# AutoThresholdPulseSensor.net
KiCad netlist of a schematic drawn in EAGLE
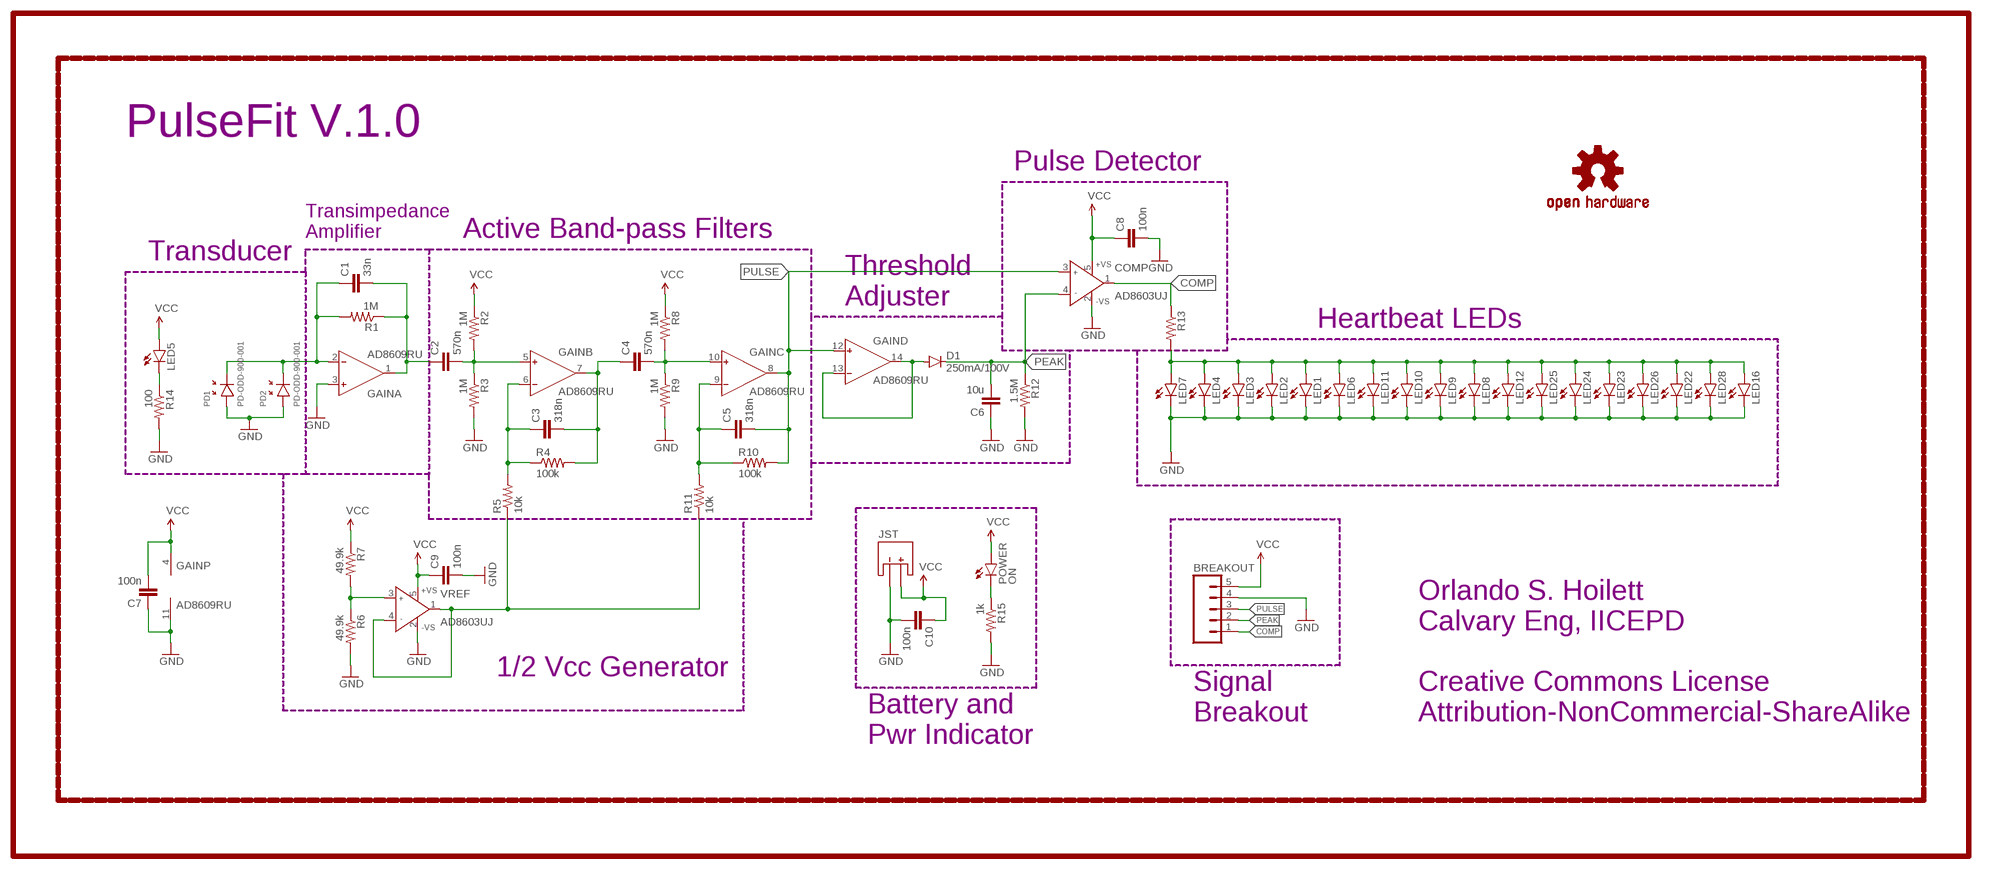
[diagram p0: schematic, sheet 1]

(export (version "E")
  (design (tool "Eeschema 10.0.6"))
  (components
    (comp (ref "BREAKOUT")
      (value "M05NO_SILK")
      (footprint "eagle-import:1X05_NO_SILK")
      (libsource (lib "eagle-import") (part "M05NO_SILK"))
    )
    (comp (ref "C1")
      (value "33n")
      (footprint "eagle-import:C0402")
      (libsource (lib "eagle-import") (part "C-EUC0402"))
    )
    (comp (ref "C2")
      (value "570n")
      (footprint "eagle-import:C0402")
      (libsource (lib "eagle-import") (part "C-EUC0402"))
    )
    (comp (ref "C3")
      (value "318n")
      (footprint "eagle-import:C0402")
      (libsource (lib "eagle-import") (part "C-EUC0402"))
    )
    (comp (ref "C4")
      (value "570n")
      (footprint "eagle-import:C0402")
      (libsource (lib "eagle-import") (part "C-EUC0402"))
    )
    (comp (ref "C5")
      (value "318n")
      (footprint "eagle-import:C0402")
      (libsource (lib "eagle-import") (part "C-EUC0402"))
    )
    (comp (ref "C6")
      (value "10u")
      (footprint "eagle-import:C0402")
      (libsource (lib "eagle-import") (part "C-EUC0402"))
    )
    (comp (ref "C7")
      (value "100n")
      (footprint "eagle-import:C0402")
      (libsource (lib "eagle-import") (part "C-EUC0402"))
    )
    (comp (ref "C8")
      (value "100n")
      (footprint "eagle-import:C0402")
      (libsource (lib "eagle-import") (part "C-EUC0402"))
    )
    (comp (ref "C9")
      (value "100n")
      (footprint "eagle-import:C0402")
      (libsource (lib "eagle-import") (part "C-EUC0402"))
    )
    (comp (ref "C10")
      (value "100n")
      (footprint "eagle-import:C0402")
      (libsource (lib "eagle-import") (part "C-EUC0402"))
    )
    (comp (ref "COMP")
      (value "AD8603UJ")
      (footprint "eagle-import:SOT23-5")
      (fields (field (name "MF") "ALTERA CORPORATION") (field (name "MPN") "AD8603AUJZ-REEL7"))
      (libsource (lib "eagle-import") (part "AD8603UJ"))
    )
    (comp (ref "D1")
      (value "250mA/100V")
      (footprint "eagle-import:SOD-323")
      (libsource (lib "eagle-import") (part "DIODEBAS16"))
    )
    (comp (ref "GAIN")
      (value "AD8609RU")
      (footprint "eagle-import:TSSOP14")
      (fields (field (name "MF") "ALTERA CORPORATION") (field (name "MPN") "AD8609ARUZ"))
      (libsource (lib "eagle-import") (part "AD8609RU"))
    )
    (comp (ref "JST")
      (value "JST-PTH")
      (footprint "eagle-import:JST-2-PTH-VERT")
      (libsource (lib "eagle-import") (part "JST-PTH"))
    )
    (comp (ref "LED1")
      (value "LED5MM")
      (footprint "eagle-import:LED5MM")
      (libsource (lib "eagle-import") (part "LED5MM"))
    )
    (comp (ref "LED2")
      (value "LED5MM")
      (footprint "eagle-import:LED5MM")
      (libsource (lib "eagle-import") (part "LED5MM"))
    )
    (comp (ref "LED3")
      (value "LED5MM")
      (footprint "eagle-import:LED5MM")
      (libsource (lib "eagle-import") (part "LED5MM"))
    )
    (comp (ref "LED4")
      (value "LED5MM")
      (footprint "eagle-import:LED5MM")
      (libsource (lib "eagle-import") (part "LED5MM"))
    )
    (comp (ref "LED5")
      (value "LED0603")
      (footprint "eagle-import:LED-0603")
      (libsource (lib "eagle-import") (part "LED0603"))
    )
    (comp (ref "LED6")
      (value "LED5MM")
      (footprint "eagle-import:LED5MM")
      (libsource (lib "eagle-import") (part "LED5MM"))
    )
    (comp (ref "LED7")
      (value "LED5MM")
      (footprint "eagle-import:LED5MM")
      (libsource (lib "eagle-import") (part "LED5MM"))
    )
    (comp (ref "LED8")
      (value "LED5MM")
      (footprint "eagle-import:LED5MM")
      (libsource (lib "eagle-import") (part "LED5MM"))
    )
    (comp (ref "LED9")
      (value "LED5MM")
      (footprint "eagle-import:LED5MM")
      (libsource (lib "eagle-import") (part "LED5MM"))
    )
    (comp (ref "LED10")
      (value "LED5MM")
      (footprint "eagle-import:LED5MM")
      (libsource (lib "eagle-import") (part "LED5MM"))
    )
    (comp (ref "LED11")
      (value "LED5MM")
      (footprint "eagle-import:LED5MM")
      (libsource (lib "eagle-import") (part "LED5MM"))
    )
    (comp (ref "LED12")
      (value "LED5MM")
      (footprint "eagle-import:LED5MM")
      (libsource (lib "eagle-import") (part "LED5MM"))
    )
    (comp (ref "LED16")
      (value "LED5MM")
      (footprint "eagle-import:LED5MM")
      (libsource (lib "eagle-import") (part "LED5MM"))
    )
    (comp (ref "LED22")
      (value "LED5MM")
      (footprint "eagle-import:LED5MM")
      (libsource (lib "eagle-import") (part "LED5MM"))
    )
    (comp (ref "LED23")
      (value "LED5MM")
      (footprint "eagle-import:LED5MM")
      (libsource (lib "eagle-import") (part "LED5MM"))
    )
    (comp (ref "LED24")
      (value "LED5MM")
      (footprint "eagle-import:LED5MM")
      (libsource (lib "eagle-import") (part "LED5MM"))
    )
    (comp (ref "LED25")
      (value "LED5MM")
      (footprint "eagle-import:LED5MM")
      (libsource (lib "eagle-import") (part "LED5MM"))
    )
    (comp (ref "LED26")
      (value "LED5MM")
      (footprint "eagle-import:LED5MM")
      (libsource (lib "eagle-import") (part "LED5MM"))
    )
    (comp (ref "LED28")
      (value "LED5MM")
      (footprint "eagle-import:LED5MM")
      (libsource (lib "eagle-import") (part "LED5MM"))
    )
    (comp (ref "LOGO1")
      (value "OSHW-LOGOS")
      (footprint "eagle-import:OSHW-LOGO-S")
      (libsource (lib "eagle-import") (part "OSHW-LOGOS"))
    )
    (comp (ref "PD1")
      (value "PD-ODD-900-001")
      (footprint "eagle-import:SMD-PD-01")
      (libsource (lib "eagle-import") (part "PD-ODD-900-001"))
    )
    (comp (ref "PD2")
      (value "PD-ODD-900-001")
      (footprint "eagle-import:SMD-PD-01")
      (libsource (lib "eagle-import") (part "PD-ODD-900-001"))
    )
    (comp (ref "POWER")
      (value "ON")
      (footprint "eagle-import:LED-0603")
      (libsource (lib "eagle-import") (part "LED0603"))
    )
    (comp (ref "R1")
      (value "1M")
      (footprint "eagle-import:R0402")
      (libsource (lib "eagle-import") (part "R-US_R0402"))
    )
    (comp (ref "R2")
      (value "1M")
      (footprint "eagle-import:R0402")
      (libsource (lib "eagle-import") (part "R-US_R0402"))
    )
    (comp (ref "R3")
      (value "1M")
      (footprint "eagle-import:R0402")
      (libsource (lib "eagle-import") (part "R-US_R0402"))
    )
    (comp (ref "R4")
      (value "100k")
      (footprint "eagle-import:R0402")
      (libsource (lib "eagle-import") (part "R-US_R0402"))
    )
    (comp (ref "R5")
      (value "10k")
      (footprint "eagle-import:R0402")
      (libsource (lib "eagle-import") (part "R-US_R0402"))
    )
    (comp (ref "R6")
      (value "49.9k")
      (footprint "eagle-import:R0402")
      (libsource (lib "eagle-import") (part "R-US_R0402"))
    )
    (comp (ref "R7")
      (value "49.9k")
      (footprint "eagle-import:R0402")
      (libsource (lib "eagle-import") (part "R-US_R0402"))
    )
    (comp (ref "R8")
      (value "1M")
      (footprint "eagle-import:R0402")
      (libsource (lib "eagle-import") (part "R-US_R0402"))
    )
    (comp (ref "R9")
      (value "1M")
      (footprint "eagle-import:R0402")
      (libsource (lib "eagle-import") (part "R-US_R0402"))
    )
    (comp (ref "R10")
      (value "100k")
      (footprint "eagle-import:R0402")
      (libsource (lib "eagle-import") (part "R-US_R0402"))
    )
    (comp (ref "R11")
      (value "10k")
      (footprint "eagle-import:R0402")
      (libsource (lib "eagle-import") (part "R-US_R0402"))
    )
    (comp (ref "R12")
      (value "1.5M")
      (footprint "eagle-import:R0402")
      (libsource (lib "eagle-import") (part "R-US_R0402"))
    )
    (comp (ref "R13")
      (value "R-US_R0402")
      (footprint "eagle-import:R0402")
      (libsource (lib "eagle-import") (part "R-US_R0402"))
    )
    (comp (ref "R14")
      (value "100")
      (footprint "eagle-import:R0402")
      (libsource (lib "eagle-import") (part "R-US_R0402"))
    )
    (comp (ref "R15")
      (value "1k")
      (footprint "eagle-import:R0402")
      (libsource (lib "eagle-import") (part "R-US_R0402"))
    )
    (comp (ref "VREF")
      (value "AD8603UJ")
      (footprint "eagle-import:SOT23-5")
      (fields (field (name "MF") "ALTERA CORPORATION") (field (name "MPN") "AD8603AUJZ-REEL7"))
      (libsource (lib "eagle-import") (part "AD8603UJ"))
    )
  )
  (nets
    (net (code "1") (name "COMP") (class "Default")
      (node (ref "BREAKOUT") (pin "1") (pinfunction "1_1") (pintype "passive"))
      (node (ref "COMP") (pin "1") (pinfunction "OUT_1") (pintype "output"))
      (node (ref "R13") (pin "1") (pinfunction "1_1") (pintype "passive"))
    )
    (net (code "2") (name "GND") (class "Default")
      (node (ref "BREAKOUT") (pin "4") (pinfunction "4_4") (pintype "passive"))
      (node (ref "C10") (pin "2") (pinfunction "2_2") (pintype "passive"))
      (node (ref "C6") (pin "1") (pinfunction "1_1") (pintype "passive"))
      (node (ref "C7") (pin "1") (pinfunction "1_1") (pintype "passive"))
      (node (ref "C8") (pin "2") (pinfunction "2_2") (pintype "passive"))
      (node (ref "C9") (pin "2") (pinfunction "2_2") (pintype "passive"))
      (node (ref "COMP") (pin "2") (pinfunction "-VS_2") (pintype "input"))
      (node (ref "GAIN") (pin "11") (pinfunction "V-_11") (pintype "power_in"))
      (node (ref "GAIN") (pin "3") (pinfunction "IN+_3") (pintype "input"))
      (node (ref "JST") (pin "-") (pinfunction "-_-") (pintype "bidirectional"))
      (node (ref "LED1") (pin "K") (pinfunction "C_K") (pintype "passive"))
      (node (ref "LED10") (pin "K") (pinfunction "C_K") (pintype "passive"))
      (node (ref "LED11") (pin "K") (pinfunction "C_K") (pintype "passive"))
      (node (ref "LED12") (pin "K") (pinfunction "C_K") (pintype "passive"))
      (node (ref "LED16") (pin "K") (pinfunction "C_K") (pintype "passive"))
      (node (ref "LED2") (pin "K") (pinfunction "C_K") (pintype "passive"))
      (node (ref "LED22") (pin "K") (pinfunction "C_K") (pintype "passive"))
      (node (ref "LED23") (pin "K") (pinfunction "C_K") (pintype "passive"))
      (node (ref "LED24") (pin "K") (pinfunction "C_K") (pintype "passive"))
      (node (ref "LED25") (pin "K") (pinfunction "C_K") (pintype "passive"))
      (node (ref "LED26") (pin "K") (pinfunction "C_K") (pintype "passive"))
      (node (ref "LED28") (pin "K") (pinfunction "C_K") (pintype "passive"))
      (node (ref "LED3") (pin "K") (pinfunction "C_K") (pintype "passive"))
      (node (ref "LED4") (pin "K") (pinfunction "C_K") (pintype "passive"))
      (node (ref "LED6") (pin "K") (pinfunction "C_K") (pintype "passive"))
      (node (ref "LED7") (pin "K") (pinfunction "C_K") (pintype "passive"))
      (node (ref "LED8") (pin "K") (pinfunction "C_K") (pintype "passive"))
      (node (ref "LED9") (pin "K") (pinfunction "C_K") (pintype "passive"))
      (node (ref "PD1") (pin "ANODE") (pinfunction "+_ANODE") (pintype "bidirectional"))
      (node (ref "PD2") (pin "ANODE") (pinfunction "+_ANODE") (pintype "bidirectional"))
      (node (ref "R12") (pin "2") (pinfunction "2_2") (pintype "passive"))
      (node (ref "R14") (pin "2") (pinfunction "2_2") (pintype "passive"))
      (node (ref "R15") (pin "2") (pinfunction "2_2") (pintype "passive"))
      (node (ref "R3") (pin "2") (pinfunction "2_2") (pintype "passive"))
      (node (ref "R6") (pin "2") (pinfunction "2_2") (pintype "passive"))
      (node (ref "R9") (pin "2") (pinfunction "2_2") (pintype "passive"))
      (node (ref "VREF") (pin "2") (pinfunction "-VS_2") (pintype "input"))
    )
    (net (code "3") (name "Net-(GAINA-IN-)") (class "Default")
      (node (ref "C1") (pin "1") (pinfunction "1_1") (pintype "passive"))
      (node (ref "GAIN") (pin "2") (pinfunction "IN-_2") (pintype "input"))
      (node (ref "PD1") (pin "CATHODE") (pinfunction "-_CATHODE") (pintype "bidirectional"))
      (node (ref "PD2") (pin "CATHODE") (pinfunction "-_CATHODE") (pintype "bidirectional"))
      (node (ref "R1") (pin "2") (pinfunction "2_2") (pintype "passive"))
    )
    (net (code "4") (name "Net-(GAINA-OUT)") (class "Default")
      (node (ref "C1") (pin "2") (pinfunction "2_2") (pintype "passive"))
      (node (ref "C2") (pin "1") (pinfunction "1_1") (pintype "passive"))
      (node (ref "GAIN") (pin "1") (pinfunction "OUT_1") (pintype "output"))
      (node (ref "R1") (pin "1") (pinfunction "1_1") (pintype "passive"))
    )
    (net (code "5") (name "Net-(GAINB-IN+)") (class "Default")
      (node (ref "C2") (pin "2") (pinfunction "2_2") (pintype "passive"))
      (node (ref "GAIN") (pin "5") (pinfunction "IN+_5") (pintype "input"))
      (node (ref "R2") (pin "2") (pinfunction "2_2") (pintype "passive"))
      (node (ref "R3") (pin "1") (pinfunction "1_1") (pintype "passive"))
    )
    (net (code "6") (name "Net-(GAINB-IN-)") (class "Default")
      (node (ref "C3") (pin "1") (pinfunction "1_1") (pintype "passive"))
      (node (ref "GAIN") (pin "6") (pinfunction "IN-_6") (pintype "input"))
      (node (ref "R4") (pin "1") (pinfunction "1_1") (pintype "passive"))
      (node (ref "R5") (pin "2") (pinfunction "2_2") (pintype "passive"))
    )
    (net (code "7") (name "Net-(GAINB-OUT)") (class "Default")
      (node (ref "C3") (pin "2") (pinfunction "2_2") (pintype "passive"))
      (node (ref "C4") (pin "1") (pinfunction "1_1") (pintype "passive"))
      (node (ref "GAIN") (pin "7") (pinfunction "OUT_7") (pintype "output"))
      (node (ref "R4") (pin "2") (pinfunction "2_2") (pintype "passive"))
    )
    (net (code "8") (name "Net-(GAINC-IN+)") (class "Default")
      (node (ref "C4") (pin "2") (pinfunction "2_2") (pintype "passive"))
      (node (ref "GAIN") (pin "10") (pinfunction "IN+_10") (pintype "input"))
      (node (ref "R8") (pin "2") (pinfunction "2_2") (pintype "passive"))
      (node (ref "R9") (pin "1") (pinfunction "1_1") (pintype "passive"))
    )
    (net (code "9") (name "Net-(GAINC-IN-)") (class "Default")
      (node (ref "C5") (pin "1") (pinfunction "1_1") (pintype "passive"))
      (node (ref "GAIN") (pin "9") (pinfunction "IN-_9") (pintype "input"))
      (node (ref "R10") (pin "1") (pinfunction "1_1") (pintype "passive"))
      (node (ref "R11") (pin "2") (pinfunction "2_2") (pintype "passive"))
    )
    (net (code "10") (name "Net-(GAIND-IN-)") (class "Default")
      (node (ref "D1") (pin "A") (pinfunction "A_A") (pintype "passive"))
      (node (ref "GAIN") (pin "13") (pinfunction "IN-_13") (pintype "input"))
      (node (ref "GAIN") (pin "14") (pinfunction "OUT_14") (pintype "output"))
    )
    (net (code "11") (name "Net-(LED1-PadA)") (class "Default")
      (node (ref "LED1") (pin "A") (pinfunction "A_A") (pintype "passive"))
      (node (ref "LED10") (pin "A") (pinfunction "A_A") (pintype "passive"))
      (node (ref "LED11") (pin "A") (pinfunction "A_A") (pintype "passive"))
      (node (ref "LED12") (pin "A") (pinfunction "A_A") (pintype "passive"))
      (node (ref "LED16") (pin "A") (pinfunction "A_A") (pintype "passive"))
      (node (ref "LED2") (pin "A") (pinfunction "A_A") (pintype "passive"))
      (node (ref "LED22") (pin "A") (pinfunction "A_A") (pintype "passive"))
      (node (ref "LED23") (pin "A") (pinfunction "A_A") (pintype "passive"))
      (node (ref "LED24") (pin "A") (pinfunction "A_A") (pintype "passive"))
      (node (ref "LED25") (pin "A") (pinfunction "A_A") (pintype "passive"))
      (node (ref "LED26") (pin "A") (pinfunction "A_A") (pintype "passive"))
      (node (ref "LED28") (pin "A") (pinfunction "A_A") (pintype "passive"))
      (node (ref "LED3") (pin "A") (pinfunction "A_A") (pintype "passive"))
      (node (ref "LED4") (pin "A") (pinfunction "A_A") (pintype "passive"))
      (node (ref "LED6") (pin "A") (pinfunction "A_A") (pintype "passive"))
      (node (ref "LED7") (pin "A") (pinfunction "A_A") (pintype "passive"))
      (node (ref "LED8") (pin "A") (pinfunction "A_A") (pintype "passive"))
      (node (ref "LED9") (pin "A") (pinfunction "A_A") (pintype "passive"))
      (node (ref "R13") (pin "2") (pinfunction "2_2") (pintype "passive"))
    )
    (net (code "12") (name "Net-(LED5-PadC)") (class "Default")
      (node (ref "LED5") (pin "C") (pinfunction "C_C") (pintype "passive"))
      (node (ref "R14") (pin "1") (pinfunction "1_1") (pintype "passive"))
    )
    (net (code "13") (name "Net-(POWER-PadC)") (class "Default")
      (node (ref "POWER") (pin "C") (pinfunction "C_C") (pintype "passive"))
      (node (ref "R15") (pin "1") (pinfunction "1_1") (pintype "passive"))
    )
    (net (code "14") (name "Net-(VREF-IN+)") (class "Default")
      (node (ref "R6") (pin "1") (pinfunction "1_1") (pintype "passive"))
      (node (ref "R7") (pin "2") (pinfunction "2_2") (pintype "passive"))
      (node (ref "VREF") (pin "3") (pinfunction "IN+_3") (pintype "input"))
    )
    (net (code "15") (name "Net-(VREF-IN-)") (class "Default")
      (node (ref "R11") (pin "1") (pinfunction "1_1") (pintype "passive"))
      (node (ref "R5") (pin "1") (pinfunction "1_1") (pintype "passive"))
      (node (ref "VREF") (pin "1") (pinfunction "OUT_1") (pintype "output"))
      (node (ref "VREF") (pin "4") (pinfunction "IN-_4") (pintype "input"))
    )
    (net (code "16") (name "PEAK") (class "Default")
      (node (ref "BREAKOUT") (pin "2") (pinfunction "2_2") (pintype "passive"))
      (node (ref "C6") (pin "2") (pinfunction "2_2") (pintype "passive"))
      (node (ref "COMP") (pin "4") (pinfunction "IN-_4") (pintype "input"))
      (node (ref "D1") (pin "C") (pinfunction "C_C") (pintype "passive"))
      (node (ref "R12") (pin "1") (pinfunction "1_1") (pintype "passive"))
    )
    (net (code "17") (name "PULSE") (class "Default")
      (node (ref "BREAKOUT") (pin "3") (pinfunction "3_3") (pintype "passive"))
      (node (ref "C5") (pin "2") (pinfunction "2_2") (pintype "passive"))
      (node (ref "COMP") (pin "3") (pinfunction "IN+_3") (pintype "input"))
      (node (ref "GAIN") (pin "12") (pinfunction "IN+_12") (pintype "input"))
      (node (ref "GAIN") (pin "8") (pinfunction "OUT_8") (pintype "output"))
      (node (ref "R10") (pin "2") (pinfunction "2_2") (pintype "passive"))
    )
    (net (code "18") (name "VCC") (class "Default")
      (node (ref "BREAKOUT") (pin "5") (pinfunction "5_5") (pintype "passive"))
      (node (ref "C10") (pin "1") (pinfunction "1_1") (pintype "passive"))
      (node (ref "C7") (pin "2") (pinfunction "2_2") (pintype "passive"))
      (node (ref "C8") (pin "1") (pinfunction "1_1") (pintype "passive"))
      (node (ref "C9") (pin "1") (pinfunction "1_1") (pintype "passive"))
      (node (ref "COMP") (pin "5") (pinfunction "+VS_5") (pintype "input"))
      (node (ref "GAIN") (pin "4") (pinfunction "V+_4") (pintype "power_in"))
      (node (ref "JST") (pin "+") (pinfunction "+_+") (pintype "bidirectional"))
      (node (ref "LED5") (pin "A") (pinfunction "A_A") (pintype "passive"))
      (node (ref "POWER") (pin "A") (pinfunction "A_A") (pintype "passive"))
      (node (ref "R2") (pin "1") (pinfunction "1_1") (pintype "passive"))
      (node (ref "R7") (pin "1") (pinfunction "1_1") (pintype "passive"))
      (node (ref "R8") (pin "1") (pinfunction "1_1") (pintype "passive"))
      (node (ref "VREF") (pin "5") (pinfunction "+VS_5") (pintype "input"))
    )
  )
)
